# currentV_conditioning.net
KiCad netlist of a schematic drawn in Altium Designer
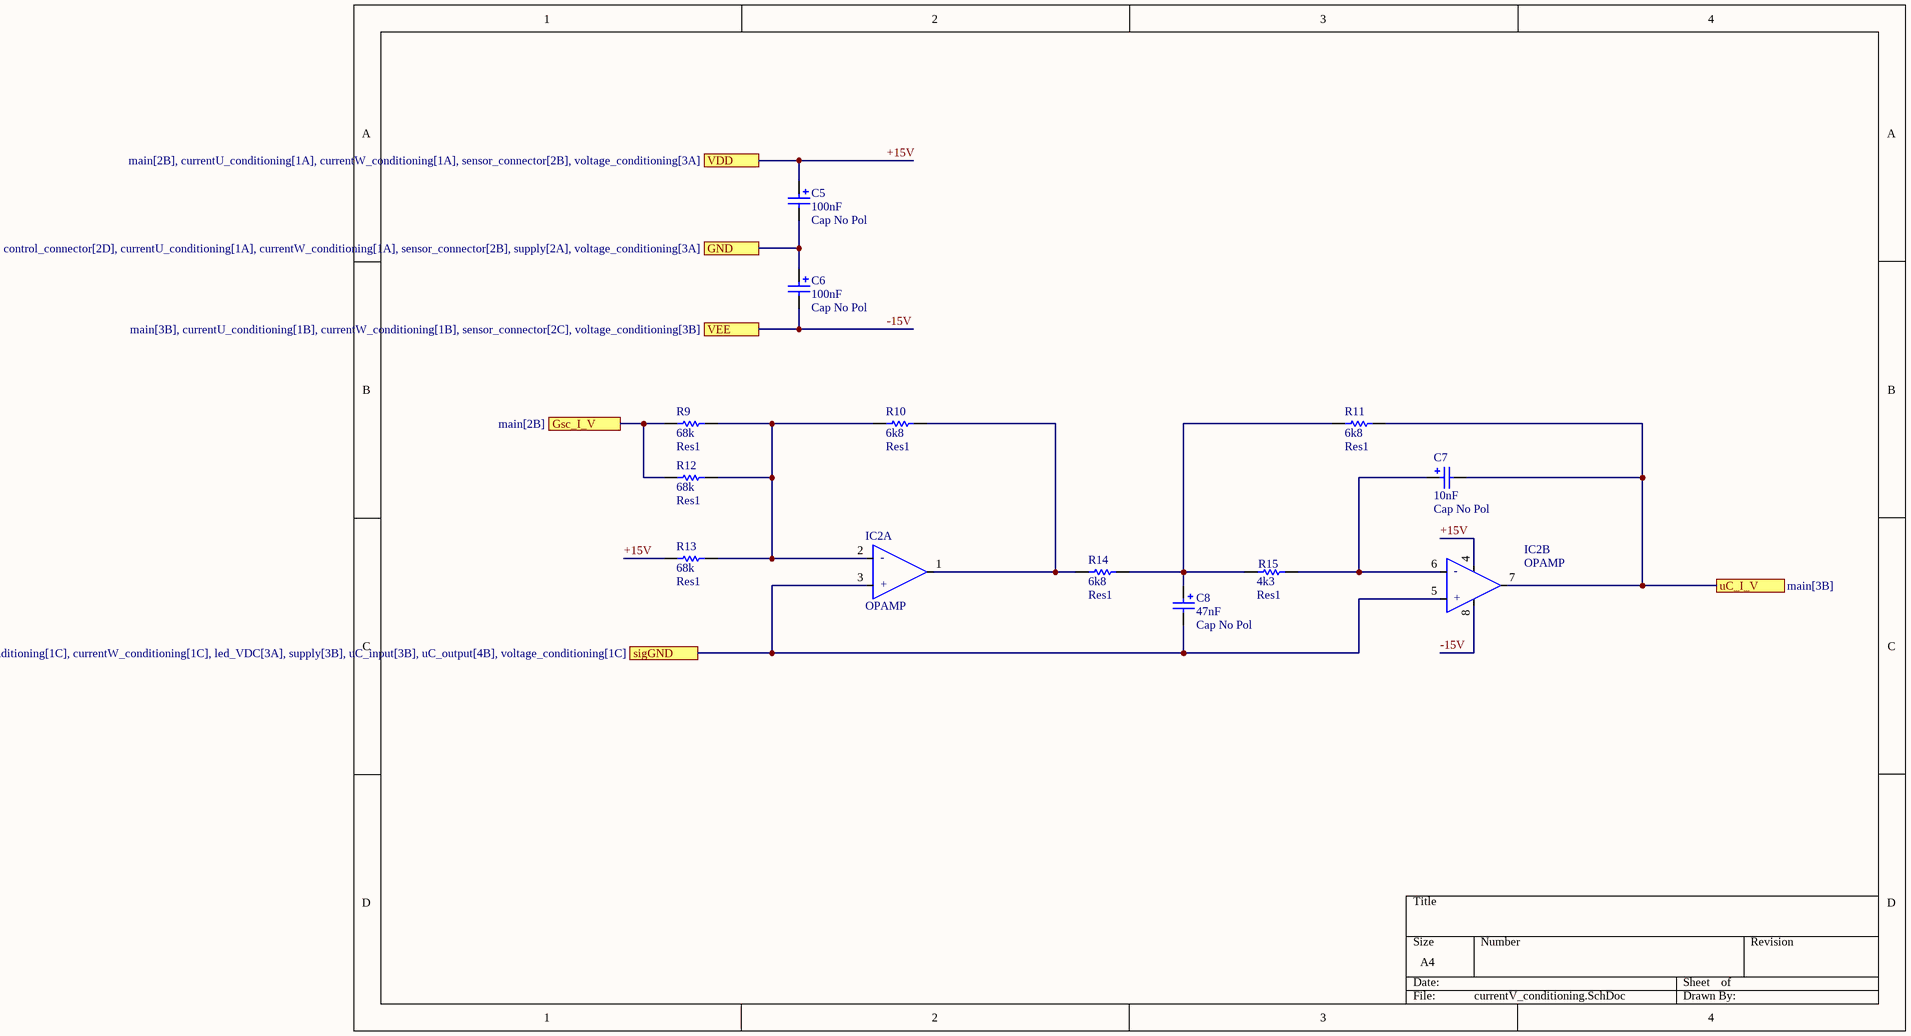
[diagram p0: currentV_conditioning.SchDoc]

(export (version "E")
  (design (tool "Eeschema 10.0.6"))
  (components
    (comp (ref "C5")
      (value "Cap No Pol")
      (footprint "RAD-0.1")
      (description "Polarized Capacitor (Radial)")
      (fields (field (name "ALTIUM_VALUE") "100nF") (field (name "PUBLISHER") "Altium Limited"))
      (libsource (lib "LABSTEPS_Project") (part "Cap No Pol"))
    )
    (comp (ref "C6")
      (value "Cap No Pol")
      (footprint "RAD-0.1")
      (description "Polarized Capacitor (Radial)")
      (fields (field (name "ALTIUM_VALUE") "100nF") (field (name "PUBLISHER") "Altium Limited"))
      (libsource (lib "LABSTEPS_Project") (part "Cap No Pol"))
    )
    (comp (ref "C7")
      (value "Cap No Pol")
      (footprint "RAD-0.1")
      (description "Polarized Capacitor (Radial)")
      (fields (field (name "ALTIUM_VALUE") "10nF") (field (name "PUBLISHER") "Altium Limited"))
      (libsource (lib "LABSTEPS_Project") (part "Cap No Pol"))
    )
    (comp (ref "C8")
      (value "Cap No Pol")
      (footprint "RAD-0.1")
      (description "Polarized Capacitor (Radial)")
      (fields (field (name "ALTIUM_VALUE") "47nF") (field (name "PUBLISHER") "Altium Limited"))
      (libsource (lib "LABSTEPS_Project") (part "Cap No Pol"))
    )
    (comp (ref "IC2")
      (value "OPAMP")
      (footprint "DIP-8")
      (description "ADTL082")
      (libsource (lib "LABSTEPS_Project") (part "ADTL082"))
    )
    (comp (ref "R9")
      (value "Res1")
      (footprint "AXIAL-0.3")
      (description "Resistor")
      (fields (field (name "ALTIUM_VALUE") "68k") (field (name "PUBLISHER") "Altium Limited"))
      (libsource (lib "LABSTEPS_Project") (part "Res1"))
    )
    (comp (ref "R10")
      (value "Res1")
      (footprint "AXIAL-0.3")
      (description "Resistor")
      (fields (field (name "ALTIUM_VALUE") "6k8") (field (name "PUBLISHER") "Altium Limited"))
      (libsource (lib "LABSTEPS_Project") (part "Res1"))
    )
    (comp (ref "R11")
      (value "Res1")
      (footprint "AXIAL-0.3")
      (description "Resistor")
      (fields (field (name "ALTIUM_VALUE") "6k8") (field (name "PUBLISHER") "Altium Limited"))
      (libsource (lib "LABSTEPS_Project") (part "Res1"))
    )
    (comp (ref "R12")
      (value "Res1")
      (footprint "AXIAL-0.3")
      (description "Resistor")
      (fields (field (name "ALTIUM_VALUE") "68k") (field (name "PUBLISHER") "Altium Limited"))
      (libsource (lib "LABSTEPS_Project") (part "Res1"))
    )
    (comp (ref "R13")
      (value "Res1")
      (footprint "AXIAL-0.3")
      (description "Resistor")
      (fields (field (name "ALTIUM_VALUE") "68k") (field (name "PUBLISHER") "Altium Limited"))
      (libsource (lib "LABSTEPS_Project") (part "Res1"))
    )
    (comp (ref "R14")
      (value "Res1")
      (footprint "AXIAL-0.3")
      (description "Resistor")
      (fields (field (name "ALTIUM_VALUE") "6k8") (field (name "PUBLISHER") "Altium Limited"))
      (libsource (lib "LABSTEPS_Project") (part "Res1"))
    )
    (comp (ref "R15")
      (value "Res1")
      (footprint "AXIAL-0.3")
      (description "Resistor")
      (fields (field (name "ALTIUM_VALUE") "4k3") (field (name "PUBLISHER") "Altium Limited"))
      (libsource (lib "LABSTEPS_Project") (part "Res1"))
    )
  )
  (nets
    (net (code "1") (name "/+15V") (class "Default")
      (node (ref "C5") (pin "1") (pinfunction "1_1") (pintype "passive"))
      (node (ref "IC2") (pin "4") (pinfunction "-V_4") (pintype "passive"))
      (node (ref "R13") (pin "1") (pinfunction "1_1") (pintype "passive"))
    )
    (net (code "2") (name "/-15V") (class "Default")
      (node (ref "C6") (pin "2") (pinfunction "2_2") (pintype "passive"))
      (node (ref "IC2") (pin "8") (pinfunction "V+_8") (pintype "passive"))
    )
    (net (code "3") (name "/GND") (class "Default")
      (node (ref "C5") (pin "2") (pinfunction "2_2") (pintype "passive"))
      (node (ref "C6") (pin "1") (pinfunction "1_1") (pintype "passive"))
    )
    (net (code "4") (name "/Gsc_I_V") (class "Default")
      (node (ref "R12") (pin "1") (pinfunction "1_1") (pintype "passive"))
      (node (ref "R9") (pin "1") (pinfunction "1_1") (pintype "passive"))
    )
    (net (code "5") (name "/sigGND") (class "Default")
      (node (ref "C8") (pin "2") (pinfunction "2_2") (pintype "passive"))
      (node (ref "IC2") (pin "3") (pinfunction "IN_A_+_3") (pintype "passive"))
      (node (ref "IC2") (pin "5") (pinfunction "IN_B_+_5") (pintype "passive"))
    )
    (net (code "6") (name "/uC_I_V") (class "Default")
      (node (ref "C7") (pin "2") (pinfunction "2_2") (pintype "passive"))
      (node (ref "IC2") (pin "7") (pinfunction "OUT_B_7") (pintype "passive"))
      (node (ref "R11") (pin "2") (pinfunction "2_2") (pintype "passive"))
    )
    (net (code "7") (name "Net-(C8-Pad1)") (class "Default")
      (node (ref "C8") (pin "1") (pinfunction "1_1") (pintype "passive"))
      (node (ref "R11") (pin "1") (pinfunction "1_1") (pintype "passive"))
      (node (ref "R14") (pin "2") (pinfunction "2_2") (pintype "passive"))
      (node (ref "R15") (pin "1") (pinfunction "1_1") (pintype "passive"))
    )
    (net (code "8") (name "Net-(IC2A-IN_A_-)") (class "Default")
      (node (ref "IC2") (pin "2") (pinfunction "IN_A_-_2") (pintype "passive"))
      (node (ref "R10") (pin "1") (pinfunction "1_1") (pintype "passive"))
      (node (ref "R12") (pin "2") (pinfunction "2_2") (pintype "passive"))
      (node (ref "R13") (pin "2") (pinfunction "2_2") (pintype "passive"))
      (node (ref "R9") (pin "2") (pinfunction "2_2") (pintype "passive"))
    )
    (net (code "9") (name "Net-(IC2A-OUT_A)") (class "Default")
      (node (ref "IC2") (pin "1") (pinfunction "OUT_A_1") (pintype "passive"))
      (node (ref "R10") (pin "2") (pinfunction "2_2") (pintype "passive"))
      (node (ref "R14") (pin "1") (pinfunction "1_1") (pintype "passive"))
    )
    (net (code "10") (name "Net-(IC2B-IN_B_-)") (class "Default")
      (node (ref "C7") (pin "1") (pinfunction "1_1") (pintype "passive"))
      (node (ref "IC2") (pin "6") (pinfunction "IN_B_-_6") (pintype "passive"))
      (node (ref "R15") (pin "2") (pinfunction "2_2") (pintype "passive"))
    )
  )
)
